# SparkFun_FreeSoC2_load.net
KiCad netlist of a schematic drawn in EAGLE
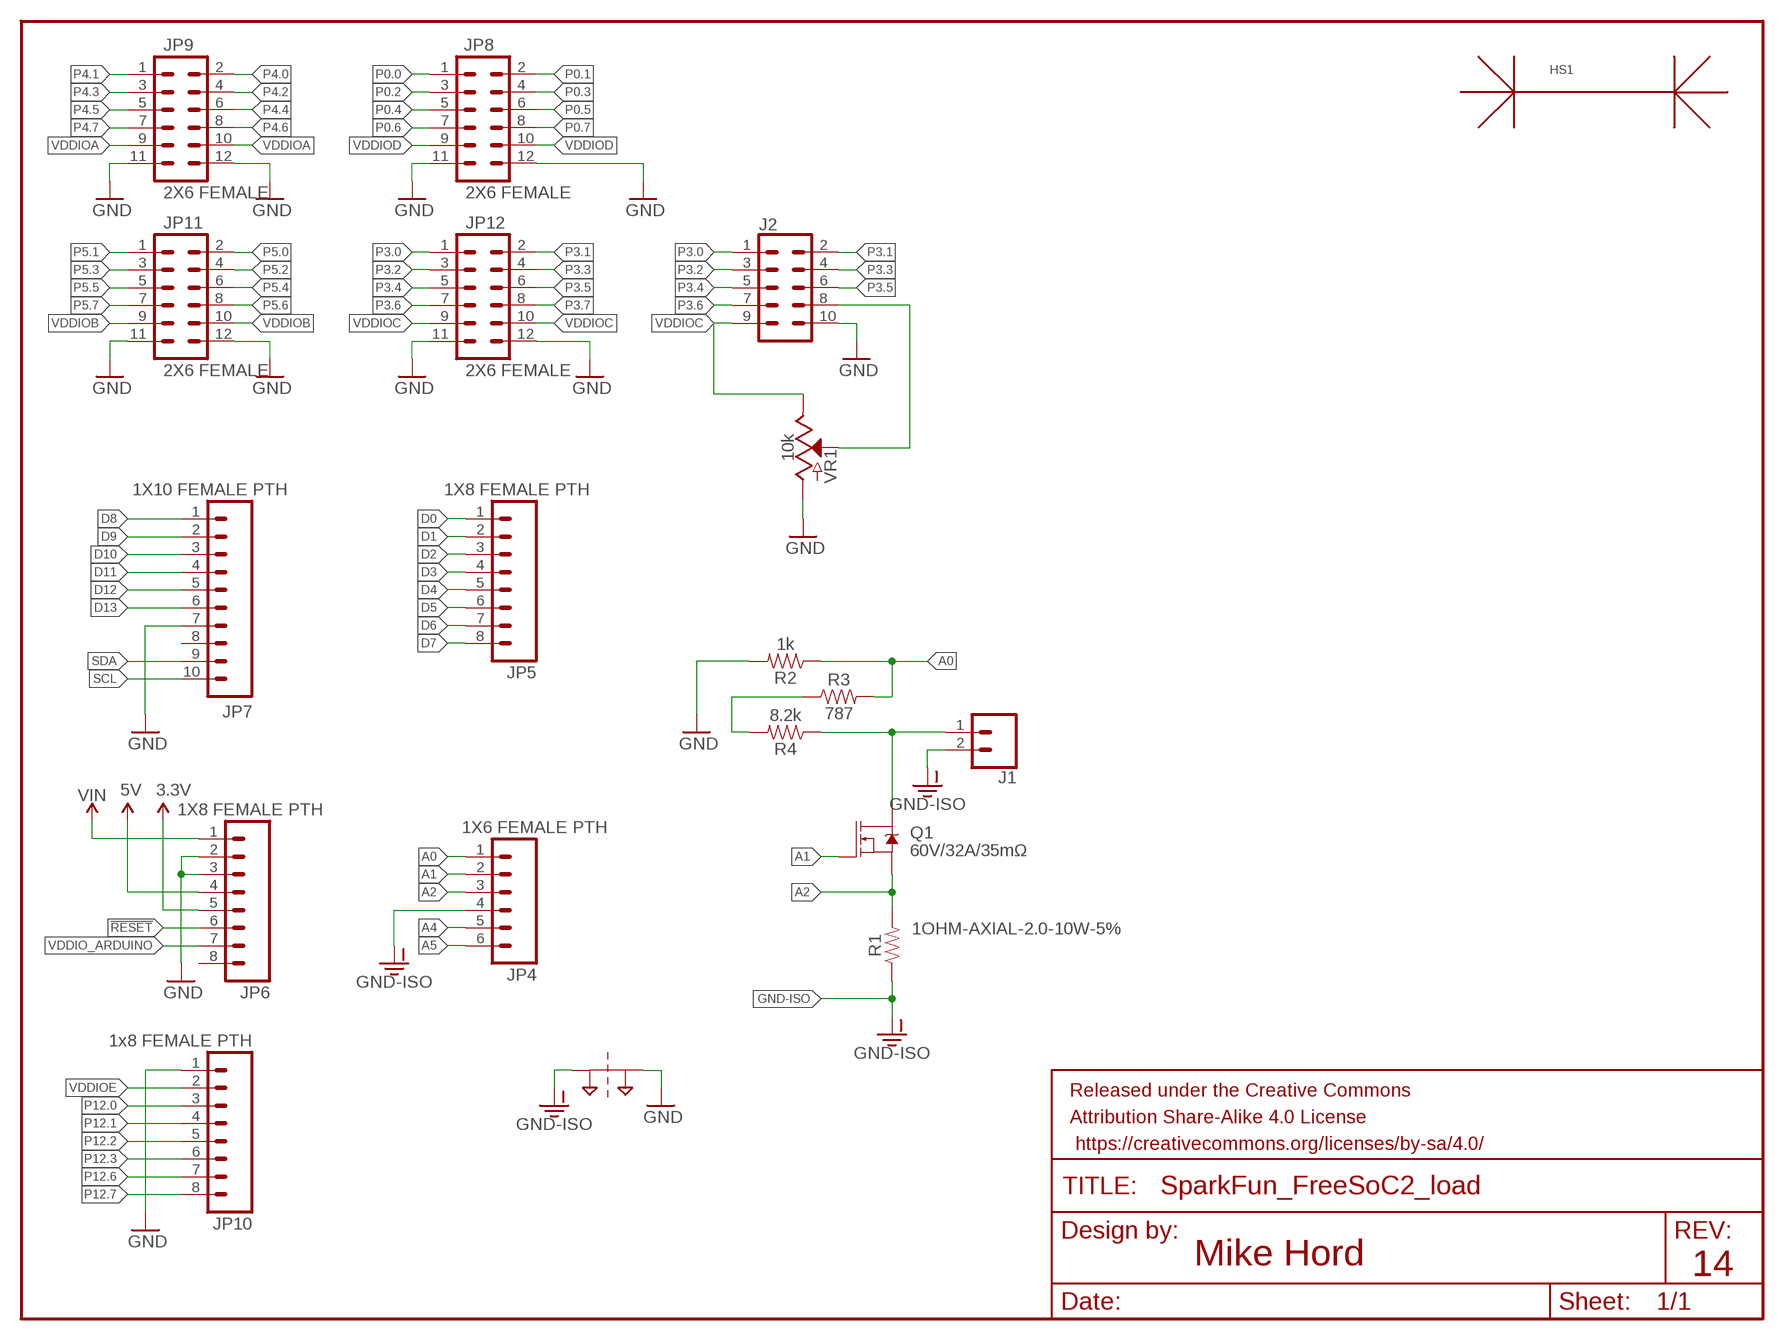
[diagram p0: schematic, sheet 1]

(export (version "E")
  (design (tool "Eeschema 10.0.6"))
  (components
    (comp (ref "FRAME3")
      (value "FRAME-LETTERNO_PACKAGE")
      (footprint "eagle-import:DUMMY")
      (fields (field (name "DESIGNER") "Nobody"))
      (libsource (lib "eagle-import") (part "FRAME-LETTERNO_PACKAGE"))
    )
    (comp (ref "HS1")
      (value "HEATSINKPRT-9576")
      (footprint "eagle-import:HEATSINK_PRT-9576")
      (libsource (lib "eagle-import") (part "HEATSINKPRT-9576"))
    )
    (comp (ref "J1")
      (value "CONN_023.5MM")
      (footprint "eagle-import:SCREWTERMINAL-3.5MM-2")
      (libsource (lib "eagle-import") (part "CONN_023.5MM"))
    )
    (comp (ref "J2")
      (value "CONN_05X2SHD")
      (footprint "eagle-import:2X5-SHROUDED")
      (libsource (lib "eagle-import") (part "CONN_05X2SHD"))
    )
    (comp (ref "JP4")
      (value "1X6 FEMALE PTH")
      (footprint "eagle-import:1X06-SIP_LOCK")
      (libsource (lib "eagle-import") (part "M06SIP_LOCK"))
    )
    (comp (ref "JP5")
      (value "1X8 FEMALE PTH")
      (footprint "eagle-import:1X08_LOCK")
      (libsource (lib "eagle-import") (part "M08LOCK"))
    )
    (comp (ref "JP6")
      (value "1X8 FEMALE PTH")
      (footprint "eagle-import:1X08_LOCK")
      (libsource (lib "eagle-import") (part "M08LOCK"))
    )
    (comp (ref "JP7")
      (value "1X10 FEMALE PTH")
      (footprint "eagle-import:1X10_LOCK")
      (libsource (lib "eagle-import") (part "M10LOCK"))
    )
    (comp (ref "JP8")
      (value "2X6 FEMALE")
      (footprint "eagle-import:2X6")
      (libsource (lib "eagle-import") (part "M06X2PTH_FEMALE"))
    )
    (comp (ref "JP9")
      (value "2X6 FEMALE")
      (footprint "eagle-import:2X6")
      (libsource (lib "eagle-import") (part "M06X2PTH_FEMALE"))
    )
    (comp (ref "JP10")
      (value "1x8 FEMALE PTH")
      (footprint "eagle-import:1X08_LOCK")
      (libsource (lib "eagle-import") (part "M08LOCK"))
    )
    (comp (ref "JP11")
      (value "2X6 FEMALE")
      (footprint "eagle-import:2X6")
      (libsource (lib "eagle-import") (part "M06X2PTH_FEMALE"))
    )
    (comp (ref "JP12")
      (value "2X6 FEMALE")
      (footprint "eagle-import:2X6")
      (libsource (lib "eagle-import") (part "M06X2PTH_FEMALE"))
    )
    (comp (ref "Q1")
      (value "60V/32A/35mΩ")
      (footprint "eagle-import:TO220V")
      (libsource (lib "eagle-import") (part "MOSFET-NCH-FQP30N06L"))
    )
    (comp (ref "R1")
      (value "1OHM-AXIAL-2.0-10W-5%")
      (footprint "eagle-import:AXIAL-2.0")
      (libsource (lib "eagle-import") (part "1OHM-AXIAL-2.0-10W-5%"))
    )
    (comp (ref "R2")
      (value "1k")
      (footprint "eagle-import:0603")
      (libsource (lib "eagle-import") (part "1KOHM-0603-1/10W-1%"))
    )
    (comp (ref "R3")
      (value "787")
      (footprint "eagle-import:0603")
      (libsource (lib "eagle-import") (part "787OHM-0603-1/10W-1%"))
    )
    (comp (ref "R4")
      (value "8.2k")
      (footprint "eagle-import:0603")
      (libsource (lib "eagle-import") (part "8.2KOHM-0603-1/10W-5%"))
    )
    (comp (ref "SUPPLY2")
      (value "2PT_GND_TIE")
      (footprint "eagle-import:2PT_GND_TIE")
      (libsource (lib "eagle-import") (part "2PT_GND_TIE"))
    )
    (comp (ref "VR1")
      (value "10k")
      (footprint "eagle-import:POT-PTH-ALPS")
      (libsource (lib "eagle-import") (part "POTENTIOMETER-PTH-9MM-1/20W-20%"))
    )
  )
  (nets
    (net (code "1") (name "/~{RESET}") (class "Default")
      (node (ref "JP6") (pin "6") (pinfunction "6_6") (pintype "passive"))
    )
    (net (code "2") (name "3.3V") (class "Default")
      (node (ref "JP6") (pin "5") (pinfunction "5_5") (pintype "passive"))
    )
    (net (code "3") (name "5V") (class "Default")
      (node (ref "JP6") (pin "4") (pinfunction "4_4") (pintype "passive"))
    )
    (net (code "4") (name "A0") (class "Default")
      (node (ref "JP4") (pin "1") (pinfunction "1_1") (pintype "passive"))
      (node (ref "R2") (pin "1") (pinfunction "1_1") (pintype "passive"))
      (node (ref "R3") (pin "2") (pinfunction "2_2") (pintype "passive"))
    )
    (net (code "5") (name "A1") (class "Default")
      (node (ref "JP4") (pin "2") (pinfunction "2_2") (pintype "passive"))
      (node (ref "Q1") (pin "1") (pinfunction "G_1") (pintype "bidirectional"))
    )
    (net (code "6") (name "A2") (class "Default")
      (node (ref "JP4") (pin "3") (pinfunction "3_3") (pintype "passive"))
      (node (ref "Q1") (pin "3") (pinfunction "S_3") (pintype "bidirectional"))
      (node (ref "R1") (pin "P$2") (pinfunction "2_P$2") (pintype "passive"))
    )
    (net (code "7") (name "A4") (class "Default")
      (node (ref "JP4") (pin "5") (pinfunction "5_5") (pintype "passive"))
    )
    (net (code "8") (name "A5") (class "Default")
      (node (ref "JP4") (pin "6") (pinfunction "6_6") (pintype "passive"))
    )
    (net (code "9") (name "D0") (class "Default")
      (node (ref "JP5") (pin "1") (pinfunction "1_1") (pintype "passive"))
    )
    (net (code "10") (name "D1") (class "Default")
      (node (ref "JP5") (pin "2") (pinfunction "2_2") (pintype "passive"))
    )
    (net (code "11") (name "D2") (class "Default")
      (node (ref "JP5") (pin "3") (pinfunction "3_3") (pintype "passive"))
    )
    (net (code "12") (name "D3") (class "Default")
      (node (ref "JP5") (pin "4") (pinfunction "4_4") (pintype "passive"))
    )
    (net (code "13") (name "D4") (class "Default")
      (node (ref "JP5") (pin "5") (pinfunction "5_5") (pintype "passive"))
    )
    (net (code "14") (name "D5") (class "Default")
      (node (ref "JP5") (pin "6") (pinfunction "6_6") (pintype "passive"))
    )
    (net (code "15") (name "D6") (class "Default")
      (node (ref "JP5") (pin "7") (pinfunction "7_7") (pintype "passive"))
    )
    (net (code "16") (name "D7") (class "Default")
      (node (ref "JP5") (pin "8") (pinfunction "8_8") (pintype "passive"))
    )
    (net (code "17") (name "D8") (class "Default")
      (node (ref "JP7") (pin "1") (pinfunction "1_1") (pintype "passive"))
    )
    (net (code "18") (name "D9") (class "Default")
      (node (ref "JP7") (pin "2") (pinfunction "2_2") (pintype "passive"))
    )
    (net (code "19") (name "D10") (class "Default")
      (node (ref "JP7") (pin "3") (pinfunction "3_3") (pintype "passive"))
    )
    (net (code "20") (name "D11") (class "Default")
      (node (ref "JP7") (pin "4") (pinfunction "4_4") (pintype "passive"))
    )
    (net (code "21") (name "D12") (class "Default")
      (node (ref "JP7") (pin "5") (pinfunction "5_5") (pintype "passive"))
    )
    (net (code "22") (name "D13") (class "Default")
      (node (ref "JP7") (pin "6") (pinfunction "6_6") (pintype "passive"))
    )
    (net (code "23") (name "GND") (class "Default")
      (node (ref "J2") (pin "10") (pinfunction "10_10") (pintype "passive"))
      (node (ref "JP10") (pin "1") (pinfunction "1_1") (pintype "passive"))
      (node (ref "JP11") (pin "11") (pinfunction "11_11") (pintype "passive"))
      (node (ref "JP11") (pin "12") (pinfunction "12_12") (pintype "passive"))
      (node (ref "JP12") (pin "11") (pinfunction "11_11") (pintype "passive"))
      (node (ref "JP12") (pin "12") (pinfunction "12_12") (pintype "passive"))
      (node (ref "JP6") (pin "2") (pinfunction "2_2") (pintype "passive"))
      (node (ref "JP6") (pin "3") (pinfunction "3_3") (pintype "passive"))
      (node (ref "JP7") (pin "7") (pinfunction "7_7") (pintype "passive"))
      (node (ref "JP8") (pin "11") (pinfunction "11_11") (pintype "passive"))
      (node (ref "JP8") (pin "12") (pinfunction "12_12") (pintype "passive"))
      (node (ref "JP9") (pin "11") (pinfunction "11_11") (pintype "passive"))
      (node (ref "JP9") (pin "12") (pinfunction "12_12") (pintype "passive"))
      (node (ref "R2") (pin "2") (pinfunction "2_2") (pintype "passive"))
      (node (ref "SUPPLY2") (pin "P$1") (pinfunction "P$1_P$1") (pintype "bidirectional"))
      (node (ref "VR1") (pin "P$3") (pinfunction "A_P$3") (pintype "passive"))
    )
    (net (code "24") (name "GND-ISO") (class "Default")
      (node (ref "J1") (pin "2") (pinfunction "2_2") (pintype "passive"))
      (node (ref "JP4") (pin "4") (pinfunction "4_4") (pintype "passive"))
      (node (ref "R1") (pin "P$1") (pinfunction "1_P$1") (pintype "passive"))
      (node (ref "SUPPLY2") (pin "P$2") (pinfunction "P$2_P$2") (pintype "bidirectional"))
    )
    (net (code "25") (name "Net-(Q1-D)") (class "Default")
      (node (ref "J1") (pin "1") (pinfunction "1_1") (pintype "passive"))
      (node (ref "Q1") (pin "2") (pinfunction "D_2") (pintype "bidirectional"))
      (node (ref "R4") (pin "1") (pinfunction "1_1") (pintype "passive"))
    )
    (net (code "26") (name "Net-(R3-Pad1)") (class "Default")
      (node (ref "R3") (pin "1") (pinfunction "1_1") (pintype "passive"))
      (node (ref "R4") (pin "2") (pinfunction "2_2") (pintype "passive"))
    )
    (net (code "27") (name "Net-(VR1-S)") (class "Default")
      (node (ref "J2") (pin "8") (pinfunction "8_8") (pintype "passive"))
      (node (ref "VR1") (pin "P$2") (pinfunction "S_P$2") (pintype "passive"))
    )
    (net (code "28") (name "P0.0") (class "Default")
      (node (ref "JP8") (pin "1") (pinfunction "1_1") (pintype "passive"))
    )
    (net (code "29") (name "P0.1") (class "Default")
      (node (ref "JP8") (pin "2") (pinfunction "2_2") (pintype "passive"))
    )
    (net (code "30") (name "P0.2") (class "Default")
      (node (ref "JP8") (pin "3") (pinfunction "3_3") (pintype "passive"))
    )
    (net (code "31") (name "P0.3") (class "Default")
      (node (ref "JP8") (pin "4") (pinfunction "4_4") (pintype "passive"))
    )
    (net (code "32") (name "P0.4") (class "Default")
      (node (ref "JP8") (pin "5") (pinfunction "5_5") (pintype "passive"))
    )
    (net (code "33") (name "P0.5") (class "Default")
      (node (ref "JP8") (pin "6") (pinfunction "6_6") (pintype "passive"))
    )
    (net (code "34") (name "P0.6") (class "Default")
      (node (ref "JP8") (pin "7") (pinfunction "7_7") (pintype "passive"))
    )
    (net (code "35") (name "P0.7") (class "Default")
      (node (ref "JP8") (pin "8") (pinfunction "8_8") (pintype "passive"))
    )
    (net (code "36") (name "P3.0") (class "Default")
      (node (ref "J2") (pin "1") (pinfunction "1_1") (pintype "passive"))
      (node (ref "JP12") (pin "1") (pinfunction "1_1") (pintype "passive"))
    )
    (net (code "37") (name "P3.1") (class "Default")
      (node (ref "J2") (pin "2") (pinfunction "2_2") (pintype "passive"))
      (node (ref "JP12") (pin "2") (pinfunction "2_2") (pintype "passive"))
    )
    (net (code "38") (name "P3.2") (class "Default")
      (node (ref "J2") (pin "3") (pinfunction "3_3") (pintype "passive"))
      (node (ref "JP12") (pin "3") (pinfunction "3_3") (pintype "passive"))
    )
    (net (code "39") (name "P3.3") (class "Default")
      (node (ref "J2") (pin "4") (pinfunction "4_4") (pintype "passive"))
      (node (ref "JP12") (pin "4") (pinfunction "4_4") (pintype "passive"))
    )
    (net (code "40") (name "P3.4") (class "Default")
      (node (ref "J2") (pin "5") (pinfunction "5_5") (pintype "passive"))
      (node (ref "JP12") (pin "5") (pinfunction "5_5") (pintype "passive"))
    )
    (net (code "41") (name "P3.5") (class "Default")
      (node (ref "J2") (pin "6") (pinfunction "6_6") (pintype "passive"))
      (node (ref "JP12") (pin "6") (pinfunction "6_6") (pintype "passive"))
    )
    (net (code "42") (name "P3.6") (class "Default")
      (node (ref "J2") (pin "7") (pinfunction "7_7") (pintype "passive"))
      (node (ref "JP12") (pin "7") (pinfunction "7_7") (pintype "passive"))
    )
    (net (code "43") (name "P3.7") (class "Default")
      (node (ref "JP12") (pin "8") (pinfunction "8_8") (pintype "passive"))
    )
    (net (code "44") (name "P4.0") (class "Default")
      (node (ref "JP9") (pin "2") (pinfunction "2_2") (pintype "passive"))
    )
    (net (code "45") (name "P4.1") (class "Default")
      (node (ref "JP9") (pin "1") (pinfunction "1_1") (pintype "passive"))
    )
    (net (code "46") (name "P4.2") (class "Default")
      (node (ref "JP9") (pin "4") (pinfunction "4_4") (pintype "passive"))
    )
    (net (code "47") (name "P4.3") (class "Default")
      (node (ref "JP9") (pin "3") (pinfunction "3_3") (pintype "passive"))
    )
    (net (code "48") (name "P4.4") (class "Default")
      (node (ref "JP9") (pin "6") (pinfunction "6_6") (pintype "passive"))
    )
    (net (code "49") (name "P4.5") (class "Default")
      (node (ref "JP9") (pin "5") (pinfunction "5_5") (pintype "passive"))
    )
    (net (code "50") (name "P4.6") (class "Default")
      (node (ref "JP9") (pin "8") (pinfunction "8_8") (pintype "passive"))
    )
    (net (code "51") (name "P4.7") (class "Default")
      (node (ref "JP9") (pin "7") (pinfunction "7_7") (pintype "passive"))
    )
    (net (code "52") (name "P5.0") (class "Default")
      (node (ref "JP11") (pin "2") (pinfunction "2_2") (pintype "passive"))
    )
    (net (code "53") (name "P5.1") (class "Default")
      (node (ref "JP11") (pin "1") (pinfunction "1_1") (pintype "passive"))
    )
    (net (code "54") (name "P5.2") (class "Default")
      (node (ref "JP11") (pin "4") (pinfunction "4_4") (pintype "passive"))
    )
    (net (code "55") (name "P5.3") (class "Default")
      (node (ref "JP11") (pin "3") (pinfunction "3_3") (pintype "passive"))
    )
    (net (code "56") (name "P5.4") (class "Default")
      (node (ref "JP11") (pin "6") (pinfunction "6_6") (pintype "passive"))
    )
    (net (code "57") (name "P5.5") (class "Default")
      (node (ref "JP11") (pin "5") (pinfunction "5_5") (pintype "passive"))
    )
    (net (code "58") (name "P5.6") (class "Default")
      (node (ref "JP11") (pin "8") (pinfunction "8_8") (pintype "passive"))
    )
    (net (code "59") (name "P5.7") (class "Default")
      (node (ref "JP11") (pin "7") (pinfunction "7_7") (pintype "passive"))
    )
    (net (code "60") (name "P12.0") (class "Default")
      (node (ref "JP10") (pin "3") (pinfunction "3_3") (pintype "passive"))
    )
    (net (code "61") (name "P12.1") (class "Default")
      (node (ref "JP10") (pin "4") (pinfunction "4_4") (pintype "passive"))
    )
    (net (code "62") (name "P12.2") (class "Default")
      (node (ref "JP10") (pin "5") (pinfunction "5_5") (pintype "passive"))
    )
    (net (code "63") (name "P12.3") (class "Default")
      (node (ref "JP10") (pin "6") (pinfunction "6_6") (pintype "passive"))
    )
    (net (code "64") (name "P12.6") (class "Default")
      (node (ref "JP10") (pin "7") (pinfunction "7_7") (pintype "passive"))
    )
    (net (code "65") (name "P12.7") (class "Default")
      (node (ref "JP10") (pin "8") (pinfunction "8_8") (pintype "passive"))
    )
    (net (code "66") (name "SCL") (class "Default")
      (node (ref "JP7") (pin "10") (pinfunction "10_10") (pintype "passive"))
    )
    (net (code "67") (name "SDA") (class "Default")
      (node (ref "JP7") (pin "9") (pinfunction "9_9") (pintype "passive"))
    )
    (net (code "68") (name "VDDIOA") (class "Default")
      (node (ref "JP9") (pin "10") (pinfunction "10_10") (pintype "passive"))
      (node (ref "JP9") (pin "9") (pinfunction "9_9") (pintype "passive"))
    )
    (net (code "69") (name "VDDIOB") (class "Default")
      (node (ref "JP11") (pin "10") (pinfunction "10_10") (pintype "passive"))
      (node (ref "JP11") (pin "9") (pinfunction "9_9") (pintype "passive"))
    )
    (net (code "70") (name "VDDIOC") (class "Default")
      (node (ref "J2") (pin "9") (pinfunction "9_9") (pintype "passive"))
      (node (ref "JP12") (pin "10") (pinfunction "10_10") (pintype "passive"))
      (node (ref "JP12") (pin "9") (pinfunction "9_9") (pintype "passive"))
      (node (ref "VR1") (pin "P$1") (pinfunction "E_P$1") (pintype "passive"))
    )
    (net (code "71") (name "VDDIOD") (class "Default")
      (node (ref "JP8") (pin "10") (pinfunction "10_10") (pintype "passive"))
      (node (ref "JP8") (pin "9") (pinfunction "9_9") (pintype "passive"))
    )
    (net (code "72") (name "VDDIOE") (class "Default")
      (node (ref "JP10") (pin "2") (pinfunction "2_2") (pintype "passive"))
    )
    (net (code "73") (name "VDDIO_ARDUINO") (class "Default")
      (node (ref "JP6") (pin "7") (pinfunction "7_7") (pintype "passive"))
    )
    (net (code "74") (name "VIN") (class "Default")
      (node (ref "JP6") (pin "1") (pinfunction "1_1") (pintype "passive"))
    )
    (net (code "75") (name "unconnected-(JP6-Pad8)") (class "Default")
      (node (ref "JP6") (pin "8") (pinfunction "8_8") (pintype "passive"))
    )
    (net (code "76") (name "unconnected-(JP7-Pad8)") (class "Default")
      (node (ref "JP7") (pin "8") (pinfunction "8_8") (pintype "passive"))
    )
  )
)
